# Schematic.net
KiCad netlist of a schematic drawn in Altium Designer
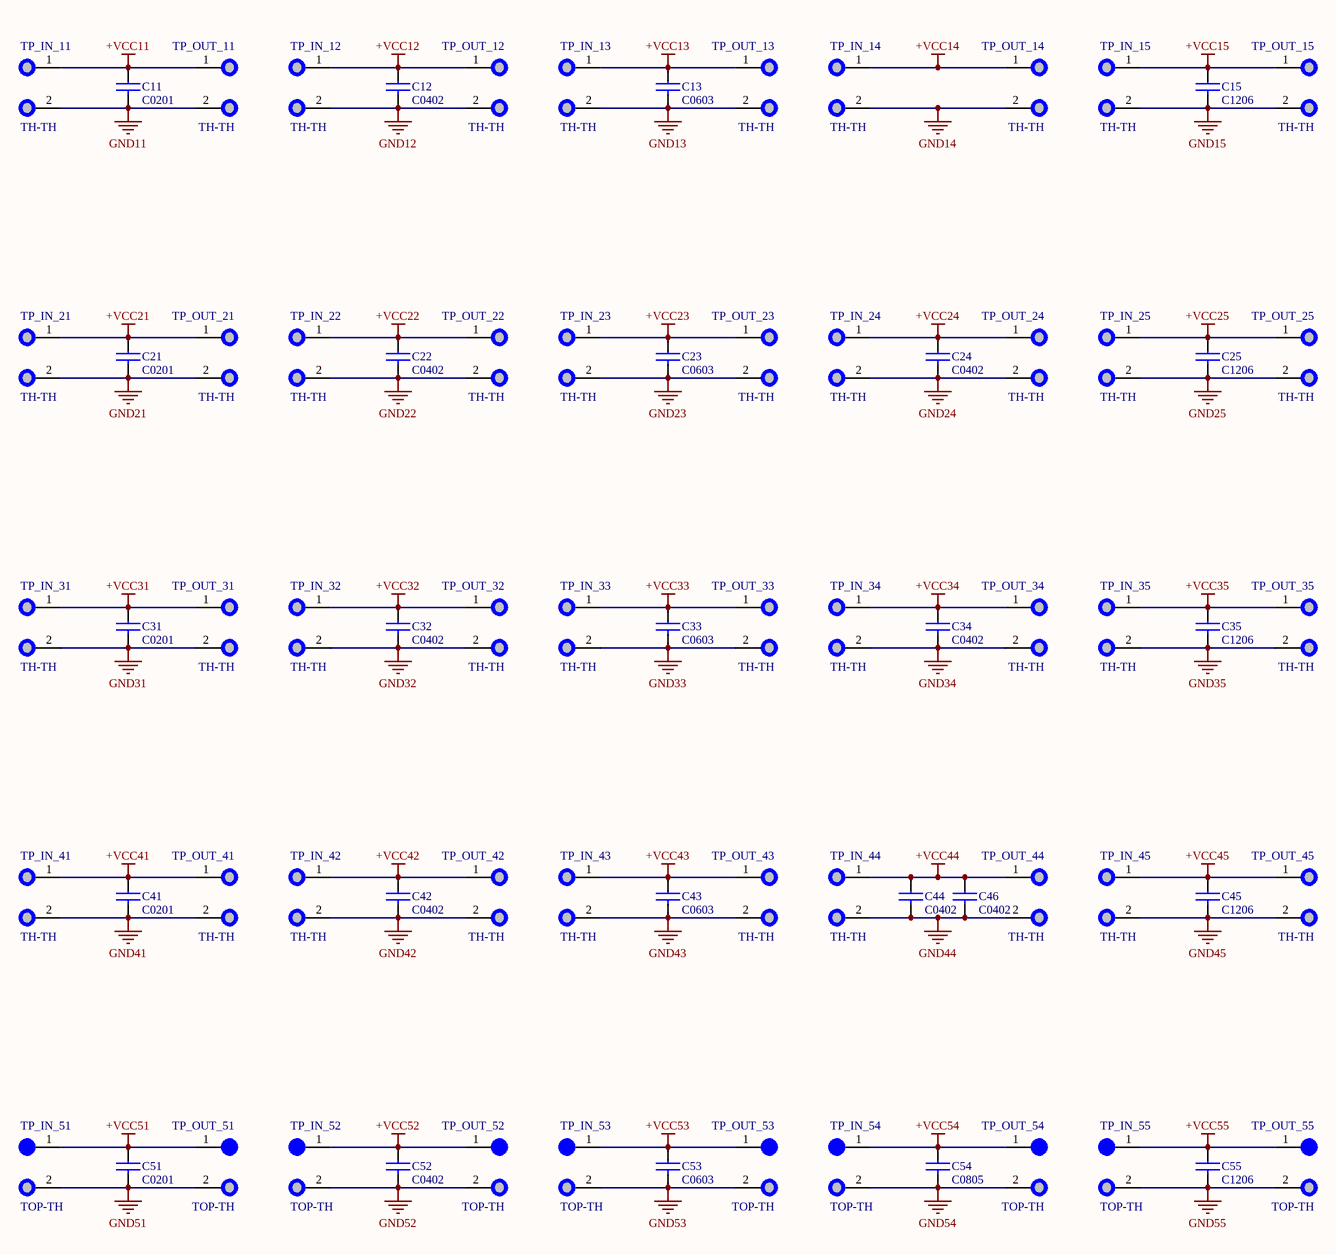
[diagram p0: Schematic.SchDoc]

(export (version "E")
  (design (tool "Eeschema 10.0.6"))
  (components
    (comp (ref "C11") (value "C0201") (footprint "C0201") (libsource (lib "Schlib") (part "CAP0201")))
    (comp (ref "C12") (value "C0402") (footprint "C0402") (libsource (lib "Schlib") (part "CAP0402")))
    (comp (ref "C13") (value "C0603") (footprint "C0603") (libsource (lib "Schlib") (part "CAP0603")))
    (comp (ref "C15") (value "C1206") (footprint "C1206") (libsource (lib "Schlib") (part "CAP1206")))
    (comp (ref "C21") (value "C0201") (footprint "C0201") (libsource (lib "Schlib") (part "CAP0201")))
    (comp (ref "C22") (value "C0402") (footprint "C0402") (libsource (lib "Schlib") (part "CAP0402")))
    (comp (ref "C23") (value "C0603") (footprint "C0603") (libsource (lib "Schlib") (part "CAP0603")))
    (comp (ref "C24") (value "C0402") (footprint "C0402") (libsource (lib "Schlib") (part "CAP0402")))
    (comp (ref "C25") (value "C1206") (footprint "C1206") (libsource (lib "Schlib") (part "CAP1206")))
    (comp (ref "C31") (value "C0201") (footprint "C0201") (libsource (lib "Schlib") (part "CAP0201")))
    (comp (ref "C32") (value "C0402") (footprint "C0402") (libsource (lib "Schlib") (part "CAP0402")))
    (comp (ref "C33") (value "C0603") (footprint "C0603") (libsource (lib "Schlib") (part "CAP0603")))
    (comp (ref "C34") (value "C0402") (footprint "C0402") (libsource (lib "Schlib") (part "CAP0402")))
    (comp (ref "C35") (value "C1206") (footprint "C1206") (libsource (lib "Schlib") (part "CAP1206")))
    (comp (ref "C41") (value "C0201") (footprint "C0201") (libsource (lib "Schlib") (part "CAP0201")))
    (comp (ref "C42") (value "C0402") (footprint "C0402") (libsource (lib "Schlib") (part "CAP0402")))
    (comp (ref "C43") (value "C0603") (footprint "C0603") (libsource (lib "Schlib") (part "CAP0603")))
    (comp (ref "C44") (value "C0402") (footprint "C0402") (libsource (lib "Schlib") (part "CAP0402")))
    (comp (ref "C45") (value "C1206") (footprint "C1206") (libsource (lib "Schlib") (part "CAP1206")))
    (comp (ref "C46") (value "C0402") (footprint "C0402") (libsource (lib "Schlib") (part "CAP0402")))
    (comp (ref "C51") (value "C0201") (footprint "C0201") (libsource (lib "Schlib") (part "CAP0201")))
    (comp (ref "C52") (value "C0402") (footprint "C0402") (libsource (lib "Schlib") (part "CAP0402")))
    (comp (ref "C53") (value "C0603") (footprint "C0603") (libsource (lib "Schlib") (part "CAP0603")))
    (comp (ref "C54") (value "C0805") (footprint "C0805") (libsource (lib "Schlib") (part "CAP0805")))
    (comp (ref "C55") (value "C1206") (footprint "C1206") (libsource (lib "Schlib") (part "CAP1206")))
    (comp (ref "TP_IN_11")
      (value "TH-TH")
      (footprint "TP_TH_TH")
      (description "Testpoints TH - TH 1mm/0.3mm")
      (libsource (lib "Schlib") (part "TP_TH_TH"))
    )
    (comp (ref "TP_IN_12")
      (value "TH-TH")
      (footprint "TP_TH_TH")
      (description "Testpoints TH - TH 1mm/0.3mm")
      (libsource (lib "Schlib") (part "TP_TH_TH"))
    )
    (comp (ref "TP_IN_13")
      (value "TH-TH")
      (footprint "TP_TH_TH")
      (description "Testpoints TH - TH 1mm/0.3mm")
      (libsource (lib "Schlib") (part "TP_TH_TH"))
    )
    (comp (ref "TP_IN_14")
      (value "TH-TH")
      (footprint "TP_TH_TH")
      (description "Testpoints TH - TH 1mm/0.3mm")
      (libsource (lib "Schlib") (part "TP_TH_TH"))
    )
    (comp (ref "TP_IN_15")
      (value "TH-TH")
      (footprint "TP_TH_TH")
      (description "Testpoints TH - TH 1mm/0.3mm")
      (libsource (lib "Schlib") (part "TP_TH_TH"))
    )
    (comp (ref "TP_IN_21")
      (value "TH-TH")
      (footprint "TP_TH_TH")
      (description "Testpoints TH - TH 1mm/0.3mm")
      (libsource (lib "Schlib") (part "TP_TH_TH"))
    )
    (comp (ref "TP_IN_22")
      (value "TH-TH")
      (footprint "TP_TH_TH")
      (description "Testpoints TH - TH 1mm/0.3mm")
      (libsource (lib "Schlib") (part "TP_TH_TH"))
    )
    (comp (ref "TP_IN_23")
      (value "TH-TH")
      (footprint "TP_TH_TH")
      (description "Testpoints TH - TH 1mm/0.3mm")
      (libsource (lib "Schlib") (part "TP_TH_TH"))
    )
    (comp (ref "TP_IN_24")
      (value "TH-TH")
      (footprint "TP_TH_TH")
      (description "Testpoints TH - TH 1mm/0.3mm")
      (libsource (lib "Schlib") (part "TP_TH_TH"))
    )
    (comp (ref "TP_IN_25")
      (value "TH-TH")
      (footprint "TP_TH_TH")
      (description "Testpoints TH - TH 1mm/0.3mm")
      (libsource (lib "Schlib") (part "TP_TH_TH"))
    )
    (comp (ref "TP_IN_31")
      (value "TH-TH")
      (footprint "TP_TH_TH")
      (description "Testpoints TH - TH 1mm/0.3mm")
      (libsource (lib "Schlib") (part "TP_TH_TH"))
    )
    (comp (ref "TP_IN_32")
      (value "TH-TH")
      (footprint "TP_TH_TH")
      (description "Testpoints TH - TH 1mm/0.3mm")
      (libsource (lib "Schlib") (part "TP_TH_TH"))
    )
    (comp (ref "TP_IN_33")
      (value "TH-TH")
      (footprint "TP_TH_TH")
      (description "Testpoints TH - TH 1mm/0.3mm")
      (libsource (lib "Schlib") (part "TP_TH_TH"))
    )
    (comp (ref "TP_IN_34")
      (value "TH-TH")
      (footprint "TP_TH_TH")
      (description "Testpoints TH - TH 1mm/0.3mm")
      (libsource (lib "Schlib") (part "TP_TH_TH"))
    )
    (comp (ref "TP_IN_35")
      (value "TH-TH")
      (footprint "TP_TH_TH")
      (description "Testpoints TH - TH 1mm/0.3mm")
      (libsource (lib "Schlib") (part "TP_TH_TH"))
    )
    (comp (ref "TP_IN_41")
      (value "TH-TH")
      (footprint "TP_TH_TH")
      (description "Testpoints TH - TH 1mm/0.3mm")
      (libsource (lib "Schlib") (part "TP_TH_TH"))
    )
    (comp (ref "TP_IN_42")
      (value "TH-TH")
      (footprint "TP_TH_TH")
      (description "Testpoints TH - TH 1mm/0.3mm")
      (libsource (lib "Schlib") (part "TP_TH_TH"))
    )
    (comp (ref "TP_IN_43")
      (value "TH-TH")
      (footprint "TP_TH_TH")
      (description "Testpoints TH - TH 1mm/0.3mm")
      (libsource (lib "Schlib") (part "TP_TH_TH"))
    )
    (comp (ref "TP_IN_44")
      (value "TH-TH")
      (footprint "TP_TH_TH")
      (description "Testpoints TH - TH 1mm/0.3mm")
      (libsource (lib "Schlib") (part "TP_TH_TH"))
    )
    (comp (ref "TP_IN_45")
      (value "TH-TH")
      (footprint "TP_TH_TH")
      (description "Testpoints TH - TH 1mm/0.3mm")
      (libsource (lib "Schlib") (part "TP_TH_TH"))
    )
    (comp (ref "TP_IN_51")
      (value "TOP-TH")
      (footprint "TP_TOP_TH")
      (description "Testpoints TOP - TH 1mm/0.3mm")
      (libsource (lib "Schlib") (part "TP_TOP_TH"))
    )
    (comp (ref "TP_IN_52")
      (value "TOP-TH")
      (footprint "TP_TOP_TH")
      (description "Testpoints TOP - TH 1mm/0.3mm")
      (libsource (lib "Schlib") (part "TP_TOP_TH"))
    )
    (comp (ref "TP_IN_53")
      (value "TOP-TH")
      (footprint "TP_TOP_TH")
      (description "Testpoints TOP - TH 1mm/0.3mm")
      (libsource (lib "Schlib") (part "TP_TOP_TH"))
    )
    (comp (ref "TP_IN_54")
      (value "TOP-TH")
      (footprint "TP_TOP_TH")
      (description "Testpoints TOP - TH 1mm/0.3mm")
      (libsource (lib "Schlib") (part "TP_TOP_TH"))
    )
    (comp (ref "TP_IN_55")
      (value "TOP-TH")
      (footprint "TP_TOP_TH")
      (description "Testpoints TOP - TH 1mm/0.3mm")
      (libsource (lib "Schlib") (part "TP_TOP_TH"))
    )
    (comp (ref "TP_OUT_11")
      (value "TH-TH")
      (footprint "TP_TH_TH")
      (description "Testpoints TH - TH 1mm/0.3mm")
      (libsource (lib "Schlib") (part "TP_TH_TH"))
    )
    (comp (ref "TP_OUT_12")
      (value "TH-TH")
      (footprint "TP_TH_TH")
      (description "Testpoints TH - TH 1mm/0.3mm")
      (libsource (lib "Schlib") (part "TP_TH_TH"))
    )
    (comp (ref "TP_OUT_13")
      (value "TH-TH")
      (footprint "TP_TH_TH")
      (description "Testpoints TH - TH 1mm/0.3mm")
      (libsource (lib "Schlib") (part "TP_TH_TH"))
    )
    (comp (ref "TP_OUT_14")
      (value "TH-TH")
      (footprint "TP_TH_TH")
      (description "Testpoints TH - TH 1mm/0.3mm")
      (libsource (lib "Schlib") (part "TP_TH_TH"))
    )
    (comp (ref "TP_OUT_15")
      (value "TH-TH")
      (footprint "TP_TH_TH")
      (description "Testpoints TH - TH 1mm/0.3mm")
      (libsource (lib "Schlib") (part "TP_TH_TH"))
    )
    (comp (ref "TP_OUT_21")
      (value "TH-TH")
      (footprint "TP_TH_TH")
      (description "Testpoints TH - TH 1mm/0.3mm")
      (libsource (lib "Schlib") (part "TP_TH_TH"))
    )
    (comp (ref "TP_OUT_22")
      (value "TH-TH")
      (footprint "TP_TH_TH")
      (description "Testpoints TH - TH 1mm/0.3mm")
      (libsource (lib "Schlib") (part "TP_TH_TH"))
    )
    (comp (ref "TP_OUT_23")
      (value "TH-TH")
      (footprint "TP_TH_TH")
      (description "Testpoints TH - TH 1mm/0.3mm")
      (libsource (lib "Schlib") (part "TP_TH_TH"))
    )
    (comp (ref "TP_OUT_24")
      (value "TH-TH")
      (footprint "TP_TH_TH")
      (description "Testpoints TH - TH 1mm/0.3mm")
      (libsource (lib "Schlib") (part "TP_TH_TH"))
    )
    (comp (ref "TP_OUT_25")
      (value "TH-TH")
      (footprint "TP_TH_TH")
      (description "Testpoints TH - TH 1mm/0.3mm")
      (libsource (lib "Schlib") (part "TP_TH_TH"))
    )
    (comp (ref "TP_OUT_31")
      (value "TH-TH")
      (footprint "TP_TH_TH")
      (description "Testpoints TH - TH 1mm/0.3mm")
      (libsource (lib "Schlib") (part "TP_TH_TH"))
    )
    (comp (ref "TP_OUT_32")
      (value "TH-TH")
      (footprint "TP_TH_TH")
      (description "Testpoints TH - TH 1mm/0.3mm")
      (libsource (lib "Schlib") (part "TP_TH_TH"))
    )
    (comp (ref "TP_OUT_33")
      (value "TH-TH")
      (footprint "TP_TH_TH")
      (description "Testpoints TH - TH 1mm/0.3mm")
      (libsource (lib "Schlib") (part "TP_TH_TH"))
    )
    (comp (ref "TP_OUT_34")
      (value "TH-TH")
      (footprint "TP_TH_TH")
      (description "Testpoints TH - TH 1mm/0.3mm")
      (libsource (lib "Schlib") (part "TP_TH_TH"))
    )
    (comp (ref "TP_OUT_35")
      (value "TH-TH")
      (footprint "TP_TH_TH")
      (description "Testpoints TH - TH 1mm/0.3mm")
      (libsource (lib "Schlib") (part "TP_TH_TH"))
    )
    (comp (ref "TP_OUT_41")
      (value "TH-TH")
      (footprint "TP_TH_TH")
      (description "Testpoints TH - TH 1mm/0.3mm")
      (libsource (lib "Schlib") (part "TP_TH_TH"))
    )
    (comp (ref "TP_OUT_42")
      (value "TH-TH")
      (footprint "TP_TH_TH")
      (description "Testpoints TH - TH 1mm/0.3mm")
      (libsource (lib "Schlib") (part "TP_TH_TH"))
    )
    (comp (ref "TP_OUT_43")
      (value "TH-TH")
      (footprint "TP_TH_TH")
      (description "Testpoints TH - TH 1mm/0.3mm")
      (libsource (lib "Schlib") (part "TP_TH_TH"))
    )
    (comp (ref "TP_OUT_44")
      (value "TH-TH")
      (footprint "TP_TH_TH")
      (description "Testpoints TH - TH 1mm/0.3mm")
      (libsource (lib "Schlib") (part "TP_TH_TH"))
    )
    (comp (ref "TP_OUT_45")
      (value "TH-TH")
      (footprint "TP_TH_TH")
      (description "Testpoints TH - TH 1mm/0.3mm")
      (libsource (lib "Schlib") (part "TP_TH_TH"))
    )
    (comp (ref "TP_OUT_51")
      (value "TOP-TH")
      (footprint "TP_TOP_TH")
      (description "Testpoints TOP - TH 1mm/0.3mm")
      (libsource (lib "Schlib") (part "TP_TOP_TH"))
    )
    (comp (ref "TP_OUT_52")
      (value "TOP-TH")
      (footprint "TP_TOP_TH")
      (description "Testpoints TOP - TH 1mm/0.3mm")
      (libsource (lib "Schlib") (part "TP_TOP_TH"))
    )
    (comp (ref "TP_OUT_53")
      (value "TOP-TH")
      (footprint "TP_TOP_TH")
      (description "Testpoints TOP - TH 1mm/0.3mm")
      (libsource (lib "Schlib") (part "TP_TOP_TH"))
    )
    (comp (ref "TP_OUT_54")
      (value "TOP-TH")
      (footprint "TP_TOP_TH")
      (description "Testpoints TOP - TH 1mm/0.3mm")
      (libsource (lib "Schlib") (part "TP_TOP_TH"))
    )
    (comp (ref "TP_OUT_55")
      (value "TOP-TH")
      (footprint "TP_TOP_TH")
      (description "Testpoints TOP - TH 1mm/0.3mm")
      (libsource (lib "Schlib") (part "TP_TOP_TH"))
    )
  )
  (nets
    (net (code "1") (name "+VCC11") (class "Default")
      (node (ref "C11") (pin "1") (pinfunction "1_1") (pintype "passive"))
      (node (ref "TP_IN_11") (pin "1") (pinfunction "1_1") (pintype "passive"))
      (node (ref "TP_OUT_11") (pin "1") (pinfunction "1_1") (pintype "passive"))
    )
    (net (code "2") (name "+VCC12") (class "Default")
      (node (ref "C12") (pin "1") (pinfunction "1_1") (pintype "passive"))
      (node (ref "TP_IN_12") (pin "1") (pinfunction "1_1") (pintype "passive"))
      (node (ref "TP_OUT_12") (pin "1") (pinfunction "1_1") (pintype "passive"))
    )
    (net (code "3") (name "+VCC13") (class "Default")
      (node (ref "C13") (pin "1") (pinfunction "1_1") (pintype "passive"))
      (node (ref "TP_IN_13") (pin "1") (pinfunction "1_1") (pintype "passive"))
      (node (ref "TP_OUT_13") (pin "1") (pinfunction "1_1") (pintype "passive"))
    )
    (net (code "4") (name "+VCC14") (class "Default")
      (node (ref "TP_IN_14") (pin "1") (pinfunction "1_1") (pintype "passive"))
      (node (ref "TP_OUT_14") (pin "1") (pinfunction "1_1") (pintype "passive"))
    )
    (net (code "5") (name "+VCC15") (class "Default")
      (node (ref "C15") (pin "1") (pinfunction "1_1") (pintype "passive"))
      (node (ref "TP_IN_15") (pin "1") (pinfunction "1_1") (pintype "passive"))
      (node (ref "TP_OUT_15") (pin "1") (pinfunction "1_1") (pintype "passive"))
    )
    (net (code "6") (name "+VCC21") (class "Default")
      (node (ref "C21") (pin "1") (pinfunction "1_1") (pintype "passive"))
      (node (ref "TP_IN_21") (pin "1") (pinfunction "1_1") (pintype "passive"))
      (node (ref "TP_OUT_21") (pin "1") (pinfunction "1_1") (pintype "passive"))
    )
    (net (code "7") (name "+VCC22") (class "Default")
      (node (ref "C22") (pin "1") (pinfunction "1_1") (pintype "passive"))
      (node (ref "TP_IN_22") (pin "1") (pinfunction "1_1") (pintype "passive"))
      (node (ref "TP_OUT_22") (pin "1") (pinfunction "1_1") (pintype "passive"))
    )
    (net (code "8") (name "+VCC23") (class "Default")
      (node (ref "C23") (pin "1") (pinfunction "1_1") (pintype "passive"))
      (node (ref "TP_IN_23") (pin "1") (pinfunction "1_1") (pintype "passive"))
      (node (ref "TP_OUT_23") (pin "1") (pinfunction "1_1") (pintype "passive"))
    )
    (net (code "9") (name "+VCC24") (class "Default")
      (node (ref "C24") (pin "1") (pinfunction "1_1") (pintype "passive"))
      (node (ref "TP_IN_24") (pin "1") (pinfunction "1_1") (pintype "passive"))
      (node (ref "TP_OUT_24") (pin "1") (pinfunction "1_1") (pintype "passive"))
    )
    (net (code "10") (name "+VCC25") (class "Default")
      (node (ref "C25") (pin "1") (pinfunction "1_1") (pintype "passive"))
      (node (ref "TP_IN_25") (pin "1") (pinfunction "1_1") (pintype "passive"))
      (node (ref "TP_OUT_25") (pin "1") (pinfunction "1_1") (pintype "passive"))
    )
    (net (code "11") (name "+VCC31") (class "Default")
      (node (ref "C31") (pin "1") (pinfunction "1_1") (pintype "passive"))
      (node (ref "TP_IN_31") (pin "1") (pinfunction "1_1") (pintype "passive"))
      (node (ref "TP_OUT_31") (pin "1") (pinfunction "1_1") (pintype "passive"))
    )
    (net (code "12") (name "+VCC32") (class "Default")
      (node (ref "C32") (pin "1") (pinfunction "1_1") (pintype "passive"))
      (node (ref "TP_IN_32") (pin "1") (pinfunction "1_1") (pintype "passive"))
      (node (ref "TP_OUT_32") (pin "1") (pinfunction "1_1") (pintype "passive"))
    )
    (net (code "13") (name "+VCC33") (class "Default")
      (node (ref "C33") (pin "1") (pinfunction "1_1") (pintype "passive"))
      (node (ref "TP_IN_33") (pin "1") (pinfunction "1_1") (pintype "passive"))
      (node (ref "TP_OUT_33") (pin "1") (pinfunction "1_1") (pintype "passive"))
    )
    (net (code "14") (name "+VCC34") (class "Default")
      (node (ref "C34") (pin "1") (pinfunction "1_1") (pintype "passive"))
      (node (ref "TP_IN_34") (pin "1") (pinfunction "1_1") (pintype "passive"))
      (node (ref "TP_OUT_34") (pin "1") (pinfunction "1_1") (pintype "passive"))
    )
    (net (code "15") (name "+VCC35") (class "Default")
      (node (ref "C35") (pin "1") (pinfunction "1_1") (pintype "passive"))
      (node (ref "TP_IN_35") (pin "1") (pinfunction "1_1") (pintype "passive"))
      (node (ref "TP_OUT_35") (pin "1") (pinfunction "1_1") (pintype "passive"))
    )
    (net (code "16") (name "+VCC41") (class "Default")
      (node (ref "C41") (pin "1") (pinfunction "1_1") (pintype "passive"))
      (node (ref "TP_IN_41") (pin "1") (pinfunction "1_1") (pintype "passive"))
      (node (ref "TP_OUT_41") (pin "1") (pinfunction "1_1") (pintype "passive"))
    )
    (net (code "17") (name "+VCC42") (class "Default")
      (node (ref "C42") (pin "1") (pinfunction "1_1") (pintype "passive"))
      (node (ref "TP_IN_42") (pin "1") (pinfunction "1_1") (pintype "passive"))
      (node (ref "TP_OUT_42") (pin "1") (pinfunction "1_1") (pintype "passive"))
    )
    (net (code "18") (name "+VCC43") (class "Default")
      (node (ref "C43") (pin "1") (pinfunction "1_1") (pintype "passive"))
      (node (ref "TP_IN_43") (pin "1") (pinfunction "1_1") (pintype "passive"))
      (node (ref "TP_OUT_43") (pin "1") (pinfunction "1_1") (pintype "passive"))
    )
    (net (code "19") (name "+VCC44") (class "Default")
      (node (ref "C44") (pin "1") (pinfunction "1_1") (pintype "passive"))
      (node (ref "C46") (pin "1") (pinfunction "1_1") (pintype "passive"))
      (node (ref "TP_IN_44") (pin "1") (pinfunction "1_1") (pintype "passive"))
      (node (ref "TP_OUT_44") (pin "1") (pinfunction "1_1") (pintype "passive"))
    )
    (net (code "20") (name "+VCC45") (class "Default")
      (node (ref "C45") (pin "1") (pinfunction "1_1") (pintype "passive"))
      (node (ref "TP_IN_45") (pin "1") (pinfunction "1_1") (pintype "passive"))
      (node (ref "TP_OUT_45") (pin "1") (pinfunction "1_1") (pintype "passive"))
    )
    (net (code "21") (name "+VCC51") (class "Default")
      (node (ref "C51") (pin "1") (pinfunction "1_1") (pintype "passive"))
      (node (ref "TP_IN_51") (pin "1") (pinfunction "1_1") (pintype "passive"))
      (node (ref "TP_OUT_51") (pin "1") (pinfunction "1_1") (pintype "passive"))
    )
    (net (code "22") (name "+VCC52") (class "Default")
      (node (ref "C52") (pin "1") (pinfunction "1_1") (pintype "passive"))
      (node (ref "TP_IN_52") (pin "1") (pinfunction "1_1") (pintype "passive"))
      (node (ref "TP_OUT_52") (pin "1") (pinfunction "1_1") (pintype "passive"))
    )
    (net (code "23") (name "+VCC53") (class "Default")
      (node (ref "C53") (pin "1") (pinfunction "1_1") (pintype "passive"))
      (node (ref "TP_IN_53") (pin "1") (pinfunction "1_1") (pintype "passive"))
      (node (ref "TP_OUT_53") (pin "1") (pinfunction "1_1") (pintype "passive"))
    )
    (net (code "24") (name "+VCC54") (class "Default")
      (node (ref "C54") (pin "1") (pinfunction "1_1") (pintype "passive"))
      (node (ref "TP_IN_54") (pin "1") (pinfunction "1_1") (pintype "passive"))
      (node (ref "TP_OUT_54") (pin "1") (pinfunction "1_1") (pintype "passive"))
    )
    (net (code "25") (name "+VCC55") (class "Default")
      (node (ref "C55") (pin "1") (pinfunction "1_1") (pintype "passive"))
      (node (ref "TP_IN_55") (pin "1") (pinfunction "1_1") (pintype "passive"))
      (node (ref "TP_OUT_55") (pin "1") (pinfunction "1_1") (pintype "passive"))
    )
    (net (code "26") (name "GND11") (class "Default")
      (node (ref "C11") (pin "2") (pinfunction "2_2") (pintype "passive"))
      (node (ref "TP_IN_11") (pin "2") (pinfunction "2_2") (pintype "passive"))
      (node (ref "TP_OUT_11") (pin "2") (pinfunction "2_2") (pintype "passive"))
    )
    (net (code "27") (name "GND12") (class "Default")
      (node (ref "C12") (pin "2") (pinfunction "2_2") (pintype "passive"))
      (node (ref "TP_IN_12") (pin "2") (pinfunction "2_2") (pintype "passive"))
      (node (ref "TP_OUT_12") (pin "2") (pinfunction "2_2") (pintype "passive"))
    )
    (net (code "28") (name "GND13") (class "Default")
      (node (ref "C13") (pin "2") (pinfunction "2_2") (pintype "passive"))
      (node (ref "TP_IN_13") (pin "2") (pinfunction "2_2") (pintype "passive"))
      (node (ref "TP_OUT_13") (pin "2") (pinfunction "2_2") (pintype "passive"))
    )
    (net (code "29") (name "GND14") (class "Default")
      (node (ref "TP_IN_14") (pin "2") (pinfunction "2_2") (pintype "passive"))
      (node (ref "TP_OUT_14") (pin "2") (pinfunction "2_2") (pintype "passive"))
    )
    (net (code "30") (name "GND15") (class "Default")
      (node (ref "C15") (pin "2") (pinfunction "2_2") (pintype "passive"))
      (node (ref "TP_IN_15") (pin "2") (pinfunction "2_2") (pintype "passive"))
      (node (ref "TP_OUT_15") (pin "2") (pinfunction "2_2") (pintype "passive"))
    )
    (net (code "31") (name "GND21") (class "Default")
      (node (ref "C21") (pin "2") (pinfunction "2_2") (pintype "passive"))
      (node (ref "TP_IN_21") (pin "2") (pinfunction "2_2") (pintype "passive"))
      (node (ref "TP_OUT_21") (pin "2") (pinfunction "2_2") (pintype "passive"))
    )
    (net (code "32") (name "GND22") (class "Default")
      (node (ref "C22") (pin "2") (pinfunction "2_2") (pintype "passive"))
      (node (ref "TP_IN_22") (pin "2") (pinfunction "2_2") (pintype "passive"))
      (node (ref "TP_OUT_22") (pin "2") (pinfunction "2_2") (pintype "passive"))
    )
    (net (code "33") (name "GND23") (class "Default")
      (node (ref "C23") (pin "2") (pinfunction "2_2") (pintype "passive"))
      (node (ref "TP_IN_23") (pin "2") (pinfunction "2_2") (pintype "passive"))
      (node (ref "TP_OUT_23") (pin "2") (pinfunction "2_2") (pintype "passive"))
    )
    (net (code "34") (name "GND24") (class "Default")
      (node (ref "C24") (pin "2") (pinfunction "2_2") (pintype "passive"))
      (node (ref "TP_IN_24") (pin "2") (pinfunction "2_2") (pintype "passive"))
      (node (ref "TP_OUT_24") (pin "2") (pinfunction "2_2") (pintype "passive"))
    )
    (net (code "35") (name "GND25") (class "Default")
      (node (ref "C25") (pin "2") (pinfunction "2_2") (pintype "passive"))
      (node (ref "TP_IN_25") (pin "2") (pinfunction "2_2") (pintype "passive"))
      (node (ref "TP_OUT_25") (pin "2") (pinfunction "2_2") (pintype "passive"))
    )
    (net (code "36") (name "GND31") (class "Default")
      (node (ref "C31") (pin "2") (pinfunction "2_2") (pintype "passive"))
      (node (ref "TP_IN_31") (pin "2") (pinfunction "2_2") (pintype "passive"))
      (node (ref "TP_OUT_31") (pin "2") (pinfunction "2_2") (pintype "passive"))
    )
    (net (code "37") (name "GND32") (class "Default")
      (node (ref "C32") (pin "2") (pinfunction "2_2") (pintype "passive"))
      (node (ref "TP_IN_32") (pin "2") (pinfunction "2_2") (pintype "passive"))
      (node (ref "TP_OUT_32") (pin "2") (pinfunction "2_2") (pintype "passive"))
    )
    (net (code "38") (name "GND33") (class "Default")
      (node (ref "C33") (pin "2") (pinfunction "2_2") (pintype "passive"))
      (node (ref "TP_IN_33") (pin "2") (pinfunction "2_2") (pintype "passive"))
      (node (ref "TP_OUT_33") (pin "2") (pinfunction "2_2") (pintype "passive"))
    )
    (net (code "39") (name "GND34") (class "Default")
      (node (ref "C34") (pin "2") (pinfunction "2_2") (pintype "passive"))
      (node (ref "TP_IN_34") (pin "2") (pinfunction "2_2") (pintype "passive"))
      (node (ref "TP_OUT_34") (pin "2") (pinfunction "2_2") (pintype "passive"))
    )
    (net (code "40") (name "GND35") (class "Default")
      (node (ref "C35") (pin "2") (pinfunction "2_2") (pintype "passive"))
      (node (ref "TP_IN_35") (pin "2") (pinfunction "2_2") (pintype "passive"))
      (node (ref "TP_OUT_35") (pin "2") (pinfunction "2_2") (pintype "passive"))
    )
    (net (code "41") (name "GND41") (class "Default")
      (node (ref "C41") (pin "2") (pinfunction "2_2") (pintype "passive"))
      (node (ref "TP_IN_41") (pin "2") (pinfunction "2_2") (pintype "passive"))
      (node (ref "TP_OUT_41") (pin "2") (pinfunction "2_2") (pintype "passive"))
    )
    (net (code "42") (name "GND42") (class "Default")
      (node (ref "C42") (pin "2") (pinfunction "2_2") (pintype "passive"))
      (node (ref "TP_IN_42") (pin "2") (pinfunction "2_2") (pintype "passive"))
      (node (ref "TP_OUT_42") (pin "2") (pinfunction "2_2") (pintype "passive"))
    )
    (net (code "43") (name "GND43") (class "Default")
      (node (ref "C43") (pin "2") (pinfunction "2_2") (pintype "passive"))
      (node (ref "TP_IN_43") (pin "2") (pinfunction "2_2") (pintype "passive"))
      (node (ref "TP_OUT_43") (pin "2") (pinfunction "2_2") (pintype "passive"))
    )
    (net (code "44") (name "GND44") (class "Default")
      (node (ref "C44") (pin "2") (pinfunction "2_2") (pintype "passive"))
      (node (ref "C46") (pin "2") (pinfunction "2_2") (pintype "passive"))
      (node (ref "TP_IN_44") (pin "2") (pinfunction "2_2") (pintype "passive"))
      (node (ref "TP_OUT_44") (pin "2") (pinfunction "2_2") (pintype "passive"))
    )
    (net (code "45") (name "GND45") (class "Default")
      (node (ref "C45") (pin "2") (pinfunction "2_2") (pintype "passive"))
      (node (ref "TP_IN_45") (pin "2") (pinfunction "2_2") (pintype "passive"))
      (node (ref "TP_OUT_45") (pin "2") (pinfunction "2_2") (pintype "passive"))
    )
    (net (code "46") (name "GND51") (class "Default")
      (node (ref "C51") (pin "2") (pinfunction "2_2") (pintype "passive"))
      (node (ref "TP_IN_51") (pin "2") (pinfunction "2_2") (pintype "passive"))
      (node (ref "TP_OUT_51") (pin "2") (pinfunction "2_2") (pintype "passive"))
    )
    (net (code "47") (name "GND52") (class "Default")
      (node (ref "C52") (pin "2") (pinfunction "2_2") (pintype "passive"))
      (node (ref "TP_IN_52") (pin "2") (pinfunction "2_2") (pintype "passive"))
      (node (ref "TP_OUT_52") (pin "2") (pinfunction "2_2") (pintype "passive"))
    )
    (net (code "48") (name "GND53") (class "Default")
      (node (ref "C53") (pin "2") (pinfunction "2_2") (pintype "passive"))
      (node (ref "TP_IN_53") (pin "2") (pinfunction "2_2") (pintype "passive"))
      (node (ref "TP_OUT_53") (pin "2") (pinfunction "2_2") (pintype "passive"))
    )
    (net (code "49") (name "GND54") (class "Default")
      (node (ref "C54") (pin "2") (pinfunction "2_2") (pintype "passive"))
      (node (ref "TP_IN_54") (pin "2") (pinfunction "2_2") (pintype "passive"))
      (node (ref "TP_OUT_54") (pin "2") (pinfunction "2_2") (pintype "passive"))
    )
    (net (code "50") (name "GND55") (class "Default")
      (node (ref "C55") (pin "2") (pinfunction "2_2") (pintype "passive"))
      (node (ref "TP_IN_55") (pin "2") (pinfunction "2_2") (pintype "passive"))
      (node (ref "TP_OUT_55") (pin "2") (pinfunction "2_2") (pintype "passive"))
    )
  )
)
